# MCU_STM32F407VGT6.net
KiCad netlist of a schematic drawn in Altium Designer
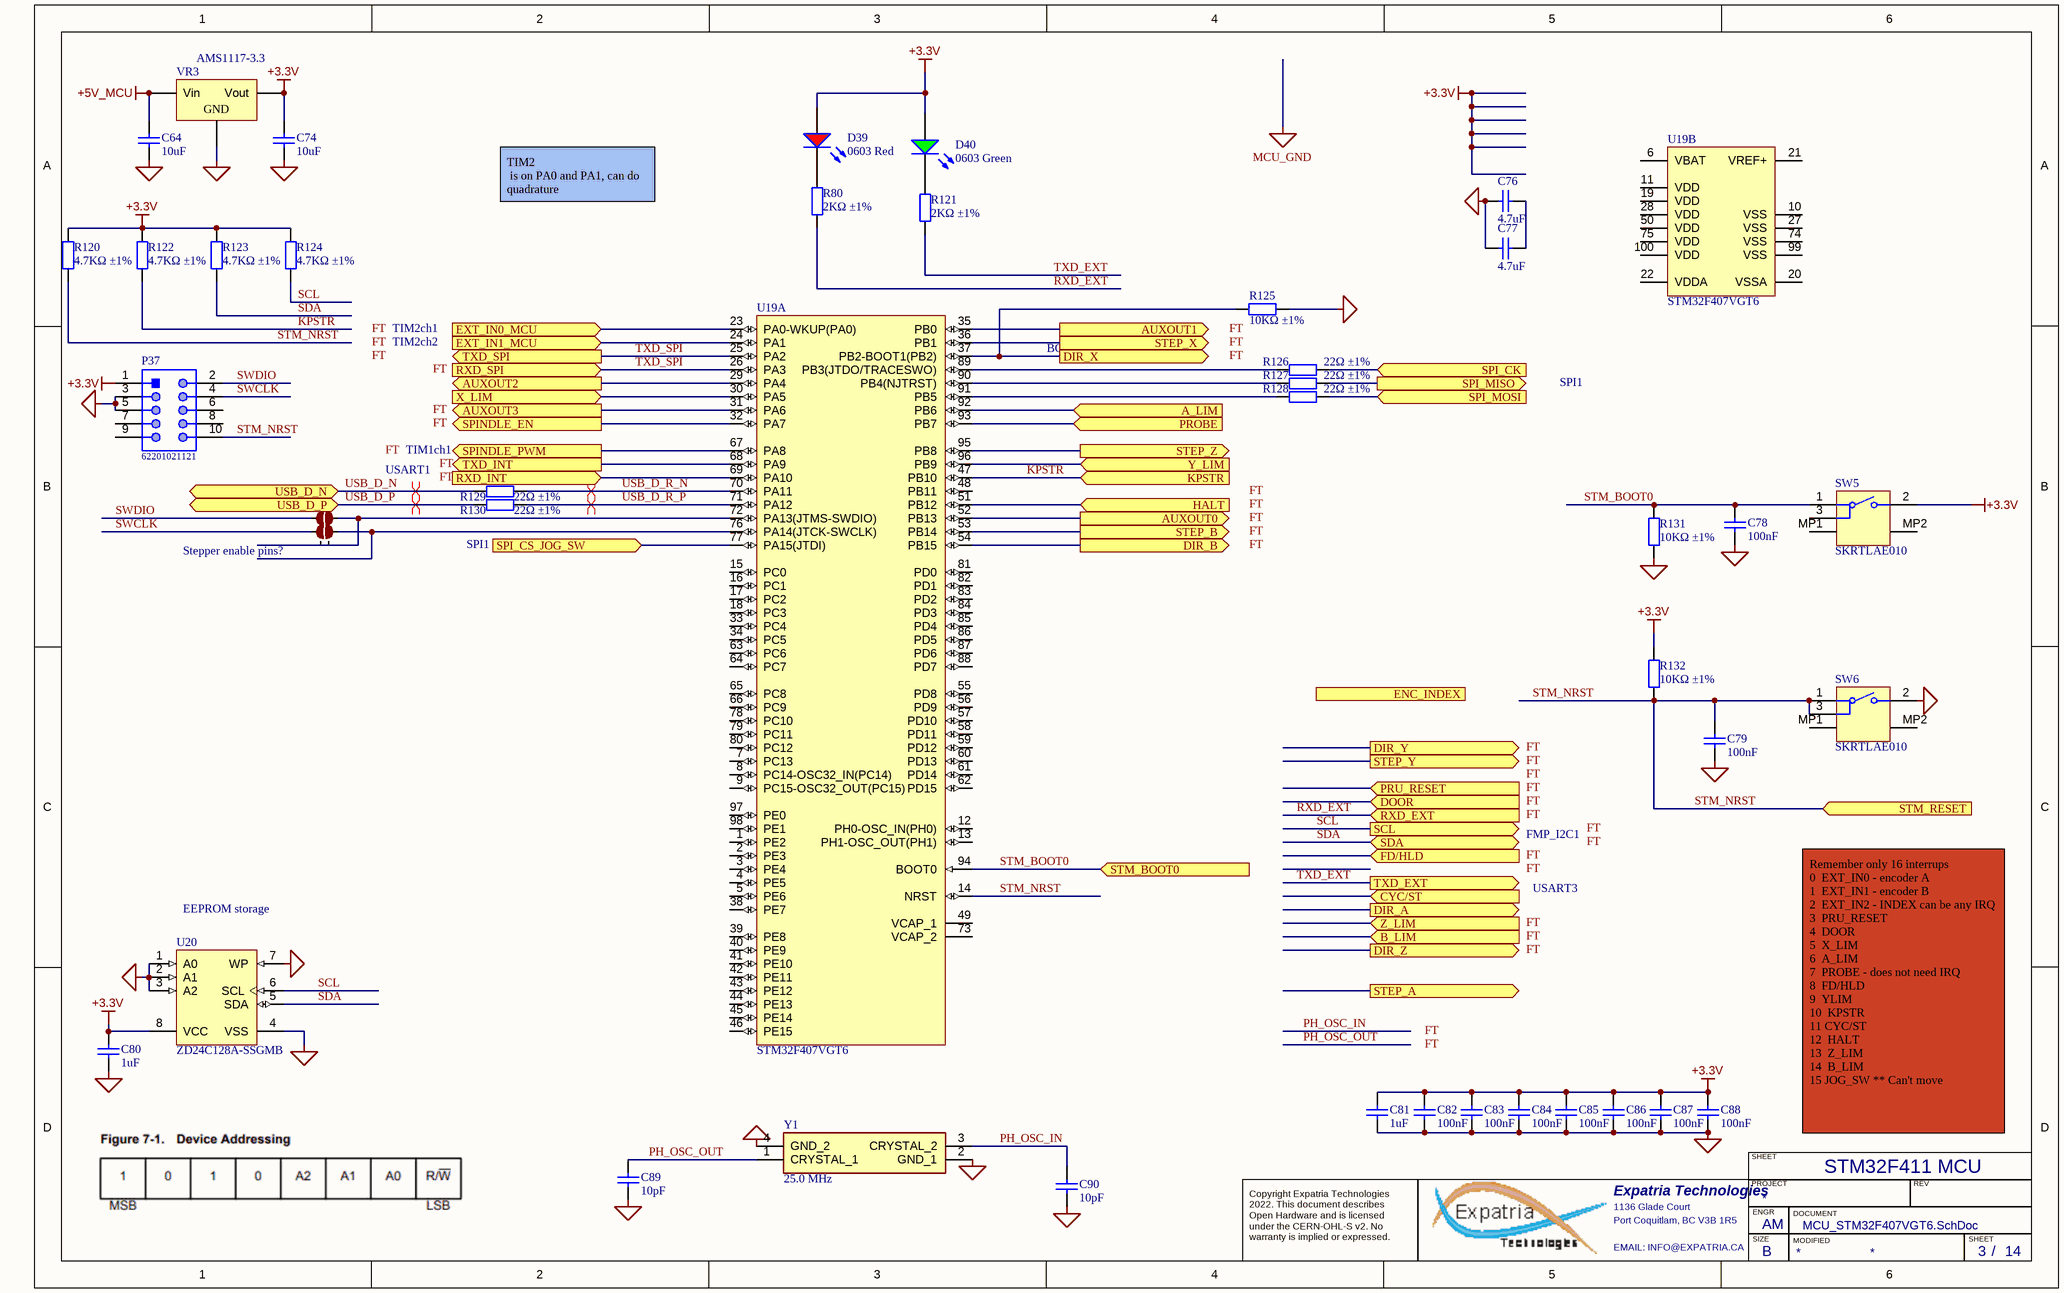
[diagram p0: MCU_STM32F407VGT6.SchDoc]

(export (version "E")
  (design (tool "Eeschema 10.0.6"))
  (components
    (comp (ref "C64")
      (value "10uF")
      (footprint "1206_C")
      (description "Chip capacitors")
      (fields
        (field (name "MANUFACTURER") "Samsung Electro-Mechanics")
        (field (name "PARTNUMBER") "CL31A106KBHNNNE")
      )
      (libsource (lib "Cap") (part "1206 10uF (106) 10% 50V"))
    )
    (comp (ref "C74")
      (value "10uF")
      (footprint "1206_C")
      (description "Chip capacitors")
      (fields
        (field (name "MANUFACTURER") "Samsung Electro-Mechanics")
        (field (name "PARTNUMBER") "CL31A106KBHNNNE")
      )
      (libsource (lib "Cap") (part "1206 10uF (106) 10% 50V"))
    )
    (comp (ref "C76")
      (value "4.7uF")
      (footprint "0603_C")
      (description "Chip capacitors")
      (fields
        (field (name "MANUFACTURER") "Samsung Electro-Mechanics")
        (field (name "PARTNUMBER") "CL10A475KO8NNNC")
      )
      (libsource (lib "Cap") (part "0603 4.7uF (475) 10% 16V"))
    )
    (comp (ref "C77")
      (value "4.7uF")
      (footprint "0603_C")
      (description "Chip capacitors")
      (fields
        (field (name "MANUFACTURER") "Samsung Electro-Mechanics")
        (field (name "PARTNUMBER") "CL10A475KO8NNNC")
      )
      (libsource (lib "Cap") (part "0603 4.7uF (475) 10% 16V"))
    )
    (comp (ref "C78")
      (value "100nF")
      (footprint "0603_C")
      (description "Chip capacitors")
      (fields (field (name "MANUFACTURER") "YAGEO") (field (name "PARTNUMBER") "CC0603KRX7R9BB104"))
      (libsource (lib "Cap") (part "0603 100nF (104) 10% 50V"))
    )
    (comp (ref "C79")
      (value "100nF")
      (footprint "0603_C")
      (description "Chip capacitors")
      (fields (field (name "MANUFACTURER") "YAGEO") (field (name "PARTNUMBER") "CC0603KRX7R9BB104"))
      (libsource (lib "Cap") (part "0603 100nF (104) 10% 50V"))
    )
    (comp (ref "C80")
      (value "1uF")
      (footprint "0603_C")
      (description "Chip capacitors")
      (fields
        (field (name "MANUFACTURER") "Samsung Electro-Mechanics")
        (field (name "PARTNUMBER") "CL10A105KB8NNNC")
      )
      (libsource (lib "Cap") (part "0603 1uF (105) 10% 50V"))
    )
    (comp (ref "C81")
      (value "1uF")
      (footprint "0603_C")
      (description "Chip capacitors")
      (fields
        (field (name "MANUFACTURER") "Samsung Electro-Mechanics")
        (field (name "PARTNUMBER") "CL10A105KB8NNNC")
      )
      (libsource (lib "Cap") (part "0603 1uF (105) 10% 50V"))
    )
    (comp (ref "C82")
      (value "100nF")
      (footprint "0603_C")
      (description "Chip capacitors")
      (fields (field (name "MANUFACTURER") "YAGEO") (field (name "PARTNUMBER") "CC0603KRX7R9BB104"))
      (libsource (lib "Cap") (part "0603 100nF (104) 10% 50V"))
    )
    (comp (ref "C83")
      (value "100nF")
      (footprint "0603_C")
      (description "Chip capacitors")
      (fields (field (name "MANUFACTURER") "YAGEO") (field (name "PARTNUMBER") "CC0603KRX7R9BB104"))
      (libsource (lib "Cap") (part "0603 100nF (104) 10% 50V"))
    )
    (comp (ref "C84")
      (value "100nF")
      (footprint "0603_C")
      (description "Chip capacitors")
      (fields (field (name "MANUFACTURER") "YAGEO") (field (name "PARTNUMBER") "CC0603KRX7R9BB104"))
      (libsource (lib "Cap") (part "0603 100nF (104) 10% 50V"))
    )
    (comp (ref "C85")
      (value "100nF")
      (footprint "0603_C")
      (description "Chip capacitors")
      (fields (field (name "MANUFACTURER") "YAGEO") (field (name "PARTNUMBER") "CC0603KRX7R9BB104"))
      (libsource (lib "Cap") (part "0603 100nF (104) 10% 50V"))
    )
    (comp (ref "C86")
      (value "100nF")
      (footprint "0603_C")
      (description "Chip capacitors")
      (fields (field (name "MANUFACTURER") "YAGEO") (field (name "PARTNUMBER") "CC0603KRX7R9BB104"))
      (libsource (lib "Cap") (part "0603 100nF (104) 10% 50V"))
    )
    (comp (ref "C87")
      (value "100nF")
      (footprint "0603_C")
      (description "Chip capacitors")
      (fields (field (name "MANUFACTURER") "YAGEO") (field (name "PARTNUMBER") "CC0603KRX7R9BB104"))
      (libsource (lib "Cap") (part "0603 100nF (104) 10% 50V"))
    )
    (comp (ref "C88")
      (value "100nF")
      (footprint "0603_C")
      (description "Chip capacitors")
      (fields (field (name "MANUFACTURER") "YAGEO") (field (name "PARTNUMBER") "CC0603KRX7R9BB104"))
      (libsource (lib "Cap") (part "0603 100nF (104) 10% 50V"))
    )
    (comp (ref "C89")
      (value "10pF")
      (footprint "0603_C")
      (description "Chip capacitors")
      (fields
        (field (name "MANUFACTURER") "Samsung Electro-Mechanics")
        (field (name "PARTNUMBER") "CL10C100JB8NNNC")
      )
      (libsource (lib "Cap") (part "0603 10pF (100) 5% 50V"))
    )
    (comp (ref "C90")
      (value "10pF")
      (footprint "0603_C")
      (description "Chip capacitors")
      (fields
        (field (name "MANUFACTURER") "Samsung Electro-Mechanics")
        (field (name "PARTNUMBER") "CL10C100JB8NNNC")
      )
      (libsource (lib "Cap") (part "0603 10pF (100) 5% 50V"))
    )
    (comp (ref "D39")
      (value "0603 Red")
      (footprint "0603_LED_S1")
      (description "LED")
      (libsource (lib "LED") (part "0603 LED Red"))
    )
    (comp (ref "D40")
      (value "0603 Green")
      (footprint "0603_LED_S1")
      (description "LED")
      (libsource (lib "LED") (part "0603 LED Green"))
    )
    (comp (ref "J14")
      (value "2 way net solder junction - Normally Open")
      (footprint "2waySolder_NO")
      (libsource (lib "PrintNC_GRBLHAL_Breakout") (part "2waySolderNO"))
    )
    (comp (ref "J15")
      (value "2 way net solder junction - Normally Open")
      (footprint "2waySolder_NO")
      (libsource (lib "PrintNC_GRBLHAL_Breakout") (part "2waySolderNO"))
    )
    (comp (ref "P37")
      (value "62201021121")
      (footprint "62201021121")
      (description "THT Vertical Pin Header WR-PHD, Pitch 1.27 mm, Dual Row, 10 pins")
      (fields (field (name "MANUFACTURER") "Wurth Elektronik") (field (name "PUBLISHER") "WurthElektronik"))
      (libsource (lib "Altium Content Vault") (part "WE-CN-2P-M-R10"))
    )
    (comp (ref "R80")
      (value "2KΩ ±1%")
      (footprint "0603_R")
      (description "Chip resistor")
      (fields (field (name "MANUFACTURER") "Uniroyal Elec") (field (name "PARTNUMBER") "0603WAF2001T5E"))
      (libsource (lib "RES") (part "0603 2K (2001) 1%"))
    )
    (comp (ref "R120")
      (value "4.7KΩ ±1%")
      (footprint "0603_R")
      (description "Chip resistor")
      (fields (field (name "MANUFACTURER") "Uniroyal Elec") (field (name "PARTNUMBER") "0603WAF4701T5E"))
      (libsource (lib "RES") (part "0603 4.7K (4701) 1%"))
    )
    (comp (ref "R121")
      (value "2KΩ ±1%")
      (footprint "0603_R")
      (description "Chip resistor")
      (fields (field (name "MANUFACTURER") "Uniroyal Elec") (field (name "PARTNUMBER") "0603WAF2001T5E"))
      (libsource (lib "RES") (part "0603 2K (2001) 1%"))
    )
    (comp (ref "R122")
      (value "4.7KΩ ±1%")
      (footprint "0603_R")
      (description "Chip resistor")
      (fields (field (name "MANUFACTURER") "Uniroyal Elec") (field (name "PARTNUMBER") "0603WAF4701T5E"))
      (libsource (lib "RES") (part "0603 4.7K (4701) 1%"))
    )
    (comp (ref "R123")
      (value "4.7KΩ ±1%")
      (footprint "0603_R")
      (description "Chip resistor")
      (fields (field (name "MANUFACTURER") "Uniroyal Elec") (field (name "PARTNUMBER") "0603WAF4701T5E"))
      (libsource (lib "RES") (part "0603 4.7K (4701) 1%"))
    )
    (comp (ref "R124")
      (value "4.7KΩ ±1%")
      (footprint "0603_R")
      (description "Chip resistor")
      (fields (field (name "MANUFACTURER") "Uniroyal Elec") (field (name "PARTNUMBER") "0603WAF4701T5E"))
      (libsource (lib "RES") (part "0603 4.7K (4701) 1%"))
    )
    (comp (ref "R125")
      (value "10KΩ ±1%")
      (footprint "0603_R")
      (description "Chip resistor")
      (fields (field (name "MANUFACTURER") "Uniroyal Elec") (field (name "PARTNUMBER") "0603WAF1002T5E"))
      (libsource (lib "RES") (part "0603 10K (1002) 1%"))
    )
    (comp (ref "R126")
      (value "22Ω ±1%")
      (footprint "0603_R")
      (description "Chip resistor")
      (fields (field (name "MANUFACTURER") "Uniroyal Elec") (field (name "PARTNUMBER") "0603WAF220JT5E"))
      (libsource (lib "") (part "0603 22R (22R0) 1%_1"))
    )
    (comp (ref "R127")
      (value "22Ω ±1%")
      (footprint "0603_R")
      (description "Chip resistor")
      (fields (field (name "MANUFACTURER") "Uniroyal Elec") (field (name "PARTNUMBER") "0603WAF220JT5E"))
      (libsource (lib "") (part "0603 22R (22R0) 1%_1"))
    )
    (comp (ref "R128")
      (value "22Ω ±1%")
      (footprint "0603_R")
      (description "Chip resistor")
      (fields (field (name "MANUFACTURER") "Uniroyal Elec") (field (name "PARTNUMBER") "0603WAF220JT5E"))
      (libsource (lib "") (part "0603 22R (22R0) 1%_1"))
    )
    (comp (ref "R129")
      (value "22Ω ±1%")
      (footprint "0603_R")
      (description "Chip resistor")
      (fields (field (name "MANUFACTURER") "Uniroyal Elec") (field (name "PARTNUMBER") "0603WAF220JT5E"))
      (libsource (lib "RES") (part "0603 22R (22R0) 1%"))
    )
    (comp (ref "R130")
      (value "22Ω ±1%")
      (footprint "0603_R")
      (description "Chip resistor")
      (fields (field (name "MANUFACTURER") "Uniroyal Elec") (field (name "PARTNUMBER") "0603WAF220JT5E"))
      (libsource (lib "RES") (part "0603 22R (22R0) 1%"))
    )
    (comp (ref "R131")
      (value "10KΩ ±1%")
      (footprint "0603_R")
      (description "Chip resistor")
      (fields (field (name "MANUFACTURER") "Uniroyal Elec") (field (name "PARTNUMBER") "0603WAF1002T5E"))
      (libsource (lib "RES") (part "0603 10K (1002) 1%"))
    )
    (comp (ref "R132")
      (value "10KΩ ±1%")
      (footprint "0603_R")
      (description "Chip resistor")
      (fields (field (name "MANUFACTURER") "Uniroyal Elec") (field (name "PARTNUMBER") "0603WAF1002T5E"))
      (libsource (lib "RES") (part "0603 10K (1002) 1%"))
    )
    (comp (ref "SW5")
      (value "SKRTLAE010")
      (footprint "ALPS-SKRTLAE010_V")
      (description "Side Push Type, 250 V, -40 to 90 degC, 3-Pin SMD, RoHS, Tape and Reel")
      (fields (field (name "MANUFACTURER") "ALPS"))
      (libsource (lib "Altium Content Vault") (part "SW_SPST-3_A"))
    )
    (comp (ref "SW6")
      (value "SKRTLAE010")
      (footprint "ALPS-SKRTLAE010_V")
      (description "Side Push Type, 250 V, -40 to 90 degC, 3-Pin SMD, RoHS, Tape and Reel")
      (fields (field (name "MANUFACTURER") "ALPS"))
      (libsource (lib "Altium Content Vault") (part "SW_SPST-3_A"))
    )
    (comp (ref "U19")
      (value "STM32F407VGT6")
      (footprint "STM-LQFP100_M")
      (fields (field (name "MANUFACTURER") "STMicroelectronics"))
      (libsource (lib "Altium Content Vault") (part "MC-ARM-STM32F40X_41X-SQ100"))
    )
    (comp (ref "U20")
      (value "ZD24C128A-SSGMB")
      (footprint "SOIC-SN8_L")
      (description "IC EEPROM 128KBIT I2C 8SOIC")
      (libsource (lib "PrintNC_GRBLHAL_Breakout") (part "MEM-SEEPROM-34AA02-IL8"))
    )
    (comp (ref "VR3")
      (value "AMS1117-3.3")
      (footprint "SOT-223")
      (description "Vout=3.3V 1A 72dB@(120Hz) (LDO)")
      (libsource (lib "LDO") (part "SOT-223 AMS1117-3.3"))
    )
    (comp (ref "Y1")
      (value "25.0 MHz")
      (footprint "SamacSys:YSX321SL")
      (description "Crystal or Oscillator")
      (fields (field (name "MANUFACTURER_PART_NUMBER") "X322525MSB4SI"))
      (libsource (lib "*") (part "YSX321SL"))
    )
  )
  (nets
    (net (code "1") (name "+3.3V") (class "Default")
      (node (ref "C74") (pin "2") (pinfunction "2_2") (pintype "passive"))
      (node (ref "C80") (pin "2") (pinfunction "2_2") (pintype "passive"))
      (node (ref "C81") (pin "2") (pinfunction "2_2") (pintype "passive"))
      (node (ref "C82") (pin "2") (pinfunction "2_2") (pintype "passive"))
      (node (ref "C83") (pin "2") (pinfunction "2_2") (pintype "passive"))
      (node (ref "C84") (pin "2") (pinfunction "2_2") (pintype "passive"))
      (node (ref "C85") (pin "2") (pinfunction "2_2") (pintype "passive"))
      (node (ref "C86") (pin "2") (pinfunction "2_2") (pintype "passive"))
      (node (ref "C87") (pin "2") (pinfunction "2_2") (pintype "passive"))
      (node (ref "C88") (pin "2") (pinfunction "2_2") (pintype "passive"))
      (node (ref "D39") (pin "A") (pinfunction "A_A") (pintype "passive"))
      (node (ref "D40") (pin "A") (pinfunction "A_A") (pintype "passive"))
      (node (ref "P37") (pin "1") (pinfunction "1_1") (pintype "passive"))
      (node (ref "R120") (pin "2") (pinfunction "2_2") (pintype "passive"))
      (node (ref "R122") (pin "2") (pinfunction "2_2") (pintype "passive"))
      (node (ref "R123") (pin "2") (pinfunction "2_2") (pintype "passive"))
      (node (ref "R124") (pin "2") (pinfunction "2_2") (pintype "passive"))
      (node (ref "R132") (pin "1") (pinfunction "1_1") (pintype "passive"))
      (node (ref "SW5") (pin "2") (pinfunction "2_2") (pintype "passive"))
      (node (ref "U20") (pin "8") (pinfunction "VCC_8") (pintype "power_in"))
      (node (ref "VR3") (pin "2") (pinfunction "Vout_2") (pintype "passive"))
    )
    (net (code "2") (name "+5V_MCU") (class "Default")
      (node (ref "C64") (pin "2") (pinfunction "2_2") (pintype "passive"))
      (node (ref "VR3") (pin "3") (pinfunction "Vin_3") (pintype "passive"))
    )
    (net (code "3") (name "/AUXOUT0") (class "Default")
      (node (ref "U19") (pin "52") (pinfunction "PB13_52") (pintype "bidirectional"))
    )
    (net (code "4") (name "/AUXOUT1") (class "Default")
      (node (ref "U19") (pin "35") (pinfunction "PB0_35") (pintype "bidirectional"))
    )
    (net (code "5") (name "/AUXOUT2") (class "Default")
      (node (ref "U19") (pin "29") (pinfunction "PA4_29") (pintype "bidirectional"))
    )
    (net (code "6") (name "/AUXOUT3") (class "Default")
      (node (ref "U19") (pin "31") (pinfunction "PA6_31") (pintype "bidirectional"))
    )
    (net (code "7") (name "/A_LIM") (class "Default")
      (node (ref "U19") (pin "92") (pinfunction "PB6_92") (pintype "bidirectional"))
    )
    (net (code "11") (name "/DIR_B") (class "Default")
      (node (ref "U19") (pin "54") (pinfunction "PB15_54") (pintype "bidirectional"))
    )
    (net (code "12") (name "/DIR_X") (class "Default")
      (node (ref "R125") (pin "2") (pinfunction "2_2") (pintype "passive"))
      (node (ref "U19") (pin "37") (pinfunction "PB2-BOOT1(PB2)_37") (pintype "bidirectional"))
    )
    (net (code "17") (name "/EXT_IN0_MCU") (class "Default")
      (node (ref "U19") (pin "23") (pinfunction "PA0-WKUP(PA0)_23") (pintype "bidirectional"))
    )
    (net (code "18") (name "/EXT_IN1_MCU") (class "Default")
      (node (ref "U19") (pin "24") (pinfunction "PA1_24") (pintype "bidirectional"))
    )
    (net (code "20") (name "/HALT") (class "Default")
      (node (ref "U19") (pin "51") (pinfunction "PB12_51") (pintype "bidirectional"))
    )
    (net (code "21") (name "/KPSTR") (class "Default")
      (node (ref "R122") (pin "1") (pinfunction "1_1") (pintype "passive"))
      (node (ref "U19") (pin "47") (pinfunction "PB10_47") (pintype "bidirectional"))
    )
    (net (code "22") (name "/PH_OSC_IN") (class "Default")
      (node (ref "C90") (pin "2") (pinfunction "2_2") (pintype "passive"))
      (node (ref "Y1") (pin "3") (pinfunction "CRYSTAL_2_3") (pintype "passive"))
    )
    (net (code "23") (name "/PH_OSC_OUT") (class "Default")
      (node (ref "C89") (pin "2") (pinfunction "2_2") (pintype "passive"))
      (node (ref "Y1") (pin "1") (pinfunction "CRYSTAL_1_1") (pintype "passive"))
    )
    (net (code "24") (name "/PROBE") (class "Default")
      (node (ref "U19") (pin "93") (pinfunction "PB7_93") (pintype "bidirectional"))
    )
    (net (code "26") (name "/RXD_EXT") (class "Default")
      (node (ref "R80") (pin "1") (pinfunction "1_1") (pintype "passive"))
    )
    (net (code "27") (name "/RXD_INT") (class "Default")
      (node (ref "U19") (pin "69") (pinfunction "PA10_69") (pintype "bidirectional"))
    )
    (net (code "28") (name "/SCL") (class "Default")
      (node (ref "R124") (pin "1") (pinfunction "1_1") (pintype "passive"))
      (node (ref "U20") (pin "6") (pinfunction "SCL_6") (pintype "input"))
    )
    (net (code "29") (name "/SDA") (class "Default")
      (node (ref "R123") (pin "1") (pinfunction "1_1") (pintype "passive"))
      (node (ref "U20") (pin "5") (pinfunction "SDA_5") (pintype "bidirectional"))
    )
    (net (code "30") (name "/SPINDLE_EN") (class "Default")
      (node (ref "U19") (pin "32") (pinfunction "PA7_32") (pintype "bidirectional"))
    )
    (net (code "31") (name "/SPINDLE_PWM") (class "Default")
      (node (ref "U19") (pin "67") (pinfunction "PA8_67") (pintype "bidirectional"))
    )
    (net (code "32") (name "/SPI_CK") (class "Default")
      (node (ref "R126") (pin "2") (pinfunction "2_2") (pintype "passive"))
    )
    (net (code "33") (name "/SPI_CS_JOG_SW") (class "Default")
      (node (ref "U19") (pin "77") (pinfunction "PA15(JTDI)_77") (pintype "bidirectional"))
    )
    (net (code "34") (name "/SPI_MISO") (class "Default")
      (node (ref "R127") (pin "2") (pinfunction "2_2") (pintype "passive"))
    )
    (net (code "35") (name "/SPI_MOSI") (class "Default")
      (node (ref "R128") (pin "2") (pinfunction "2_2") (pintype "passive"))
    )
    (net (code "37") (name "/STEP_B") (class "Default")
      (node (ref "U19") (pin "53") (pinfunction "PB14_53") (pintype "bidirectional"))
    )
    (net (code "38") (name "/STEP_X") (class "Default")
      (node (ref "U19") (pin "36") (pinfunction "PB1_36") (pintype "bidirectional"))
    )
    (net (code "40") (name "/STEP_Z") (class "Default")
      (node (ref "U19") (pin "95") (pinfunction "PB8_95") (pintype "bidirectional"))
    )
    (net (code "41") (name "/STM_BOOT0") (class "Default")
      (node (ref "C78") (pin "2") (pinfunction "2_2") (pintype "passive"))
      (node (ref "R131") (pin "1") (pinfunction "1_1") (pintype "passive"))
      (node (ref "SW5") (pin "1") (pinfunction "1_1") (pintype "passive"))
      (node (ref "U19") (pin "94") (pinfunction "BOOT0_94") (pintype "input"))
    )
    (net (code "42") (name "/STM_NRST") (class "Default")
      (node (ref "C79") (pin "2") (pinfunction "2_2") (pintype "passive"))
      (node (ref "P37") (pin "10") (pinfunction "10_10") (pintype "passive"))
      (node (ref "R120") (pin "1") (pinfunction "1_1") (pintype "passive"))
      (node (ref "R132") (pin "2") (pinfunction "2_2") (pintype "passive"))
      (node (ref "SW6") (pin "1") (pinfunction "1_1") (pintype "passive"))
      (node (ref "SW6") (pin "3") (pinfunction "3_3") (pintype "passive"))
      (node (ref "U19") (pin "14") (pinfunction "NRST_14") (pintype "bidirectional"))
    )
    (net (code "43") (name "/SWCLK") (class "Default")
      (node (ref "J15") (pin "1") (pinfunction "1_1") (pintype "passive"))
      (node (ref "P37") (pin "4") (pinfunction "4_4") (pintype "passive"))
    )
    (net (code "44") (name "/SWDIO") (class "Default")
      (node (ref "J14") (pin "1") (pinfunction "1_1") (pintype "passive"))
      (node (ref "P37") (pin "2") (pinfunction "2_2") (pintype "passive"))
    )
    (net (code "45") (name "/TXD_EXT") (class "Default")
      (node (ref "R121") (pin "1") (pinfunction "1_1") (pintype "passive"))
    )
    (net (code "46") (name "/TXD_INT") (class "Default")
      (node (ref "U19") (pin "68") (pinfunction "PA9_68") (pintype "bidirectional"))
    )
    (net (code "47") (name "/TXD_SPI") (class "Default")
      (node (ref "U19") (pin "25") (pinfunction "PA2_25") (pintype "bidirectional"))
      (node (ref "U19") (pin "26") (pinfunction "PA3_26") (pintype "bidirectional"))
    )
    (net (code "48") (name "/USB_D_N") (class "Default")
      (node (ref "R129") (pin "2") (pinfunction "2_2") (pintype "passive"))
    )
    (net (code "49") (name "/USB_D_P") (class "Default")
      (node (ref "R130") (pin "2") (pinfunction "2_2") (pintype "passive"))
    )
    (net (code "50") (name "/USB_D_R_N") (class "Default")
      (node (ref "R129") (pin "1") (pinfunction "1_1") (pintype "passive"))
      (node (ref "U19") (pin "70") (pinfunction "PA11_70") (pintype "bidirectional"))
    )
    (net (code "51") (name "/USB_D_R_P") (class "Default")
      (node (ref "R130") (pin "1") (pinfunction "1_1") (pintype "passive"))
      (node (ref "U19") (pin "71") (pinfunction "PA12_71") (pintype "bidirectional"))
    )
    (net (code "52") (name "/X_LIM") (class "Default")
      (node (ref "U19") (pin "30") (pinfunction "PA5_30") (pintype "bidirectional"))
    )
    (net (code "53") (name "/Y_LIM") (class "Default")
      (node (ref "U19") (pin "96") (pinfunction "PB9_96") (pintype "bidirectional"))
    )
    (net (code "55") (name "MCU_GND") (class "Default")
      (node (ref "C64") (pin "1") (pinfunction "1_1") (pintype "passive"))
      (node (ref "C74") (pin "1") (pinfunction "1_1") (pintype "passive"))
      (node (ref "C76") (pin "1") (pinfunction "1_1") (pintype "passive"))
      (node (ref "C77") (pin "1") (pinfunction "1_1") (pintype "passive"))
      (node (ref "C78") (pin "1") (pinfunction "1_1") (pintype "passive"))
      (node (ref "C79") (pin "1") (pinfunction "1_1") (pintype "passive"))
      (node (ref "C80") (pin "1") (pinfunction "1_1") (pintype "passive"))
      (node (ref "C81") (pin "1") (pinfunction "1_1") (pintype "passive"))
      (node (ref "C82") (pin "1") (pinfunction "1_1") (pintype "passive"))
      (node (ref "C83") (pin "1") (pinfunction "1_1") (pintype "passive"))
      (node (ref "C84") (pin "1") (pinfunction "1_1") (pintype "passive"))
      (node (ref "C85") (pin "1") (pinfunction "1_1") (pintype "passive"))
      (node (ref "C86") (pin "1") (pinfunction "1_1") (pintype "passive"))
      (node (ref "C87") (pin "1") (pinfunction "1_1") (pintype "passive"))
      (node (ref "C88") (pin "1") (pinfunction "1_1") (pintype "passive"))
      (node (ref "C89") (pin "1") (pinfunction "1_1") (pintype "passive"))
      (node (ref "C90") (pin "1") (pinfunction "1_1") (pintype "passive"))
      (node (ref "P37") (pin "3") (pinfunction "3_3") (pintype "passive"))
      (node (ref "P37") (pin "5") (pinfunction "5_5") (pintype "passive"))
      (node (ref "R125") (pin "1") (pinfunction "1_1") (pintype "passive"))
      (node (ref "R131") (pin "2") (pinfunction "2_2") (pintype "passive"))
      (node (ref "SW6") (pin "2") (pinfunction "2_2") (pintype "passive"))
      (node (ref "U20") (pin "1") (pinfunction "A0_1") (pintype "input"))
      (node (ref "U20") (pin "2") (pinfunction "A1_2") (pintype "input"))
      (node (ref "U20") (pin "3") (pinfunction "A2_3") (pintype "input"))
      (node (ref "U20") (pin "4") (pinfunction "VSS_4") (pintype "power_in"))
      (node (ref "U20") (pin "7") (pinfunction "WP_7") (pintype "input"))
      (node (ref "VR3") (pin "1") (pinfunction "GND_1") (pintype "passive"))
      (node (ref "Y1") (pin "2") (pinfunction "GND_1_2") (pintype "passive"))
      (node (ref "Y1") (pin "4") (pinfunction "GND_2_4") (pintype "passive"))
    )
    (net (code "56") (name "Net-(C76-Pad2)") (class "Default")
      (node (ref "C76") (pin "2") (pinfunction "2_2") (pintype "passive"))
      (node (ref "C77") (pin "2") (pinfunction "2_2") (pintype "passive"))
    )
    (net (code "57") (name "Net-(D39-PadK)") (class "Default")
      (node (ref "D39") (pin "K") (pinfunction "K_K") (pintype "passive"))
      (node (ref "R80") (pin "2") (pinfunction "2_2") (pintype "passive"))
    )
    (net (code "58") (name "Net-(D40-PadK)") (class "Default")
      (node (ref "D40") (pin "K") (pinfunction "K_K") (pintype "passive"))
      (node (ref "R121") (pin "2") (pinfunction "2_2") (pintype "passive"))
    )
    (net (code "59") (name "Net-(U19A-PA13(JTMS-SWDIO))") (class "Default")
      (node (ref "J14") (pin "2") (pinfunction "2_2") (pintype "passive"))
      (node (ref "U19") (pin "72") (pinfunction "PA13(JTMS-SWDIO)_72") (pintype "bidirectional"))
    )
    (net (code "60") (name "Net-(U19A-PA14(JTCK-SWCLK))") (class "Default")
      (node (ref "J15") (pin "2") (pinfunction "2_2") (pintype "passive"))
      (node (ref "U19") (pin "76") (pinfunction "PA14(JTCK-SWCLK)_76") (pintype "bidirectional"))
    )
    (net (code "61") (name "Net-(U19A-PB3(JTDO{slash}TRACESWO))") (class "Default")
      (node (ref "R126") (pin "1") (pinfunction "1_1") (pintype "passive"))
      (node (ref "U19") (pin "89") (pinfunction "PB3(JTDO/TRACESWO)_89") (pintype "bidirectional"))
    )
    (net (code "62") (name "Net-(U19A-PB4(NJTRST))") (class "Default")
      (node (ref "R127") (pin "1") (pinfunction "1_1") (pintype "passive"))
      (node (ref "U19") (pin "90") (pinfunction "PB4(NJTRST)_90") (pintype "bidirectional"))
    )
    (net (code "63") (name "Net-(U19A-PB5)") (class "Default")
      (node (ref "R128") (pin "1") (pinfunction "1_1") (pintype "passive"))
      (node (ref "U19") (pin "91") (pinfunction "PB5_91") (pintype "bidirectional"))
    )
    (net (code "64") (name "unconnected-(P37-Pad6)") (class "Default")
      (node (ref "P37") (pin "6") (pinfunction "6_6") (pintype "passive"))
    )
    (net (code "65") (name "unconnected-(P37-Pad7)") (class "Default")
      (node (ref "P37") (pin "7") (pinfunction "7_7") (pintype "passive"))
    )
    (net (code "66") (name "unconnected-(P37-Pad8)") (class "Default")
      (node (ref "P37") (pin "8") (pinfunction "8_8") (pintype "passive"))
    )
    (net (code "67") (name "unconnected-(P37-Pad9)") (class "Default")
      (node (ref "P37") (pin "9") (pinfunction "9_9") (pintype "passive"))
    )
    (net (code "68") (name "unconnected-(SW5-Pad3)") (class "Default")
      (node (ref "SW5") (pin "3") (pinfunction "3_3") (pintype "passive"))
    )
    (net (code "69") (name "unconnected-(SW5-PadMP1)") (class "Default")
      (node (ref "SW5") (pin "MP1") (pinfunction "MP1_MP1") (pintype "passive"))
    )
    (net (code "70") (name "unconnected-(SW5-PadMP2)") (class "Default")
      (node (ref "SW5") (pin "MP2") (pinfunction "MP2_MP2") (pintype "passive"))
    )
    (net (code "71") (name "unconnected-(SW6-PadMP1)") (class "Default")
      (node (ref "SW6") (pin "MP1") (pinfunction "MP1_MP1") (pintype "passive"))
    )
    (net (code "72") (name "unconnected-(SW6-PadMP2)") (class "Default")
      (node (ref "SW6") (pin "MP2") (pinfunction "MP2_MP2") (pintype "passive"))
    )
    (net (code "73") (name "unconnected-(U19A-PB11-Pad48)") (class "Default")
      (node (ref "U19") (pin "48") (pinfunction "PB11_48") (pintype "bidirectional"))
    )
    (net (code "74") (name "unconnected-(U19A-PC0-Pad15)") (class "Default")
      (node (ref "U19") (pin "15") (pinfunction "PC0_15") (pintype "bidirectional"))
    )
    (net (code "75") (name "unconnected-(U19A-PC1-Pad16)") (class "Default")
      (node (ref "U19") (pin "16") (pinfunction "PC1_16") (pintype "bidirectional"))
    )
    (net (code "76") (name "unconnected-(U19A-PC2-Pad17)") (class "Default")
      (node (ref "U19") (pin "17") (pinfunction "PC2_17") (pintype "bidirectional"))
    )
    (net (code "77") (name "unconnected-(U19A-PC3-Pad18)") (class "Default")
      (node (ref "U19") (pin "18") (pinfunction "PC3_18") (pintype "bidirectional"))
    )
    (net (code "78") (name "unconnected-(U19A-PC4-Pad33)") (class "Default")
      (node (ref "U19") (pin "33") (pinfunction "PC4_33") (pintype "bidirectional"))
    )
    (net (code "79") (name "unconnected-(U19A-PC5-Pad34)") (class "Default")
      (node (ref "U19") (pin "34") (pinfunction "PC5_34") (pintype "bidirectional"))
    )
    (net (code "80") (name "unconnected-(U19A-PC6-Pad63)") (class "Default")
      (node (ref "U19") (pin "63") (pinfunction "PC6_63") (pintype "bidirectional"))
    )
    (net (code "81") (name "unconnected-(U19A-PC7-Pad64)") (class "Default")
      (node (ref "U19") (pin "64") (pinfunction "PC7_64") (pintype "bidirectional"))
    )
    (net (code "82") (name "unconnected-(U19A-PC8-Pad65)") (class "Default")
      (node (ref "U19") (pin "65") (pinfunction "PC8_65") (pintype "bidirectional"))
    )
    (net (code "83") (name "unconnected-(U19A-PC9-Pad66)") (class "Default")
      (node (ref "U19") (pin "66") (pinfunction "PC9_66") (pintype "bidirectional"))
    )
    (net (code "84") (name "unconnected-(U19A-PC10-Pad78)") (class "Default")
      (node (ref "U19") (pin "78") (pinfunction "PC10_78") (pintype "bidirectional"))
    )
    (net (code "85") (name "unconnected-(U19A-PC11-Pad79)") (class "Default")
      (node (ref "U19") (pin "79") (pinfunction "PC11_79") (pintype "bidirectional"))
    )
    (net (code "86") (name "unconnected-(U19A-PC12-Pad80)") (class "Default")
      (node (ref "U19") (pin "80") (pinfunction "PC12_80") (pintype "bidirectional"))
    )
    (net (code "87") (name "unconnected-(U19A-PC13-Pad7)") (class "Default")
      (node (ref "U19") (pin "7") (pinfunction "PC13_7") (pintype "bidirectional"))
    )
    (net (code "88") (name "unconnected-(U19A-PC14-OSC32_IN(PC14)-Pad8)") (class "Default")
      (node (ref "U19") (pin "8") (pinfunction "PC14-OSC32_IN(PC14)_8") (pintype "bidirectional"))
    )
    (net (code "89") (name "unconnected-(U19A-PC15-OSC32_OUT(PC15)-Pad9)") (class "Default")
      (node (ref "U19") (pin "9") (pinfunction "PC15-OSC32_OUT(PC15)_9") (pintype "bidirectional"))
    )
    (net (code "90") (name "unconnected-(U19A-PD0-Pad81)") (class "Default")
      (node (ref "U19") (pin "81") (pinfunction "PD0_81") (pintype "bidirectional"))
    )
    (net (code "91") (name "unconnected-(U19A-PD1-Pad82)") (class "Default")
      (node (ref "U19") (pin "82") (pinfunction "PD1_82") (pintype "bidirectional"))
    )
    (net (code "92") (name "unconnected-(U19A-PD2-Pad83)") (class "Default")
      (node (ref "U19") (pin "83") (pinfunction "PD2_83") (pintype "bidirectional"))
    )
    (net (code "93") (name "unconnected-(U19A-PD3-Pad84)") (class "Default")
      (node (ref "U19") (pin "84") (pinfunction "PD3_84") (pintype "bidirectional"))
    )
    (net (code "94") (name "unconnected-(U19A-PD4-Pad85)") (class "Default")
      (node (ref "U19") (pin "85") (pinfunction "PD4_85") (pintype "bidirectional"))
    )
    (net (code "95") (name "unconnected-(U19A-PD5-Pad86)") (class "Default")
      (node (ref "U19") (pin "86") (pinfunction "PD5_86") (pintype "bidirectional"))
    )
    (net (code "96") (name "unconnected-(U19A-PD6-Pad87)") (class "Default")
      (node (ref "U19") (pin "87") (pinfunction "PD6_87") (pintype "bidirectional"))
    )
    (net (code "97") (name "unconnected-(U19A-PD7-Pad88)") (class "Default")
      (node (ref "U19") (pin "88") (pinfunction "PD7_88") (pintype "bidirectional"))
    )
    (net (code "98") (name "unconnected-(U19A-PD8-Pad55)") (class "Default")
      (node (ref "U19") (pin "55") (pinfunction "PD8_55") (pintype "bidirectional"))
    )
    (net (code "99") (name "unconnected-(U19A-PD9-Pad56)") (class "Default")
      (node (ref "U19") (pin "56") (pinfunction "PD9_56") (pintype "bidirectional"))
    )
    (net (code "100") (name "unconnected-(U19A-PD10-Pad57)") (class "Default")
      (node (ref "U19") (pin "57") (pinfunction "PD10_57") (pintype "bidirectional"))
    )
    (net (code "101") (name "unconnected-(U19A-PD11-Pad58)") (class "Default")
      (node (ref "U19") (pin "58") (pinfunction "PD11_58") (pintype "bidirectional"))
    )
    (net (code "102") (name "unconnected-(U19A-PD12-Pad59)") (class "Default")
      (node (ref "U19") (pin "59") (pinfunction "PD12_59") (pintype "bidirectional"))
    )
    (net (code "103") (name "unconnected-(U19A-PD13-Pad60)") (class "Default")
      (node (ref "U19") (pin "60") (pinfunction "PD13_60") (pintype "bidirectional"))
    )
    (net (code "104") (name "unconnected-(U19A-PD14-Pad61)") (class "Default")
      (node (ref "U19") (pin "61") (pinfunction "PD14_61") (pintype "bidirectional"))
    )
    (net (code "105") (name "unconnected-(U19A-PD15-Pad62)") (class "Default")
      (node (ref "U19") (pin "62") (pinfunction "PD15_62") (pintype "bidirectional"))
    )
    (net (code "106") (name "unconnected-(U19A-PE0-Pad97)") (class "Default")
      (node (ref "U19") (pin "97") (pinfunction "PE0_97") (pintype "bidirectional"))
    )
    (net (code "107") (name "unconnected-(U19A-PE1-Pad98)") (class "Default")
      (node (ref "U19") (pin "98") (pinfunction "PE1_98") (pintype "bidirectional"))
    )
    (net (code "108") (name "unconnected-(U19A-PE2-Pad1)") (class "Default")
      (node (ref "U19") (pin "1") (pinfunction "PE2_1") (pintype "bidirectional"))
    )
    (net (code "109") (name "unconnected-(U19A-PE3-Pad2)") (class "Default")
      (node (ref "U19") (pin "2") (pinfunction "PE3_2") (pintype "bidirectional"))
    )
    (net (code "110") (name "unconnected-(U19A-PE4-Pad3)") (class "Default")
      (node (ref "U19") (pin "3") (pinfunction "PE4_3") (pintype "bidirectional"))
    )
    (net (code "111") (name "unconnected-(U19A-PE5-Pad4)") (class "Default")
      (node (ref "U19") (pin "4") (pinfunction "PE5_4") (pintype "bidirectional"))
    )
    (net (code "112") (name "unconnected-(U19A-PE6-Pad5)") (class "Default")
      (node (ref "U19") (pin "5") (pinfunction "PE6_5") (pintype "bidirectional"))
    )
    (net (code "113") (name "unconnected-(U19A-PE7-Pad38)") (class "Default")
      (node (ref "U19") (pin "38") (pinfunction "PE7_38") (pintype "bidirectional"))
    )
    (net (code "114") (name "unconnected-(U19A-PE8-Pad39)") (class "Default")
      (node (ref "U19") (pin "39") (pinfunction "PE8_39") (pintype "bidirectional"))
    )
    (net (code "115") (name "unconnected-(U19A-PE9-Pad40)") (class "Default")
      (node (ref "U19") (pin "40") (pinfunction "PE9_40") (pintype "bidirectional"))
    )
    (net (code "116") (name "unconnected-(U19A-PE10-Pad41)") (class "Default")
      (node (ref "U19") (pin "41") (pinfunction "PE10_41") (pintype "bidirectional"))
    )
    (net (code "117") (name "unconnected-(U19A-PE11-Pad42)") (class "Default")
      (node (ref "U19") (pin "42") (pinfunction "PE11_42") (pintype "bidirectional"))
    )
    (net (code "118") (name "unconnected-(U19A-PE12-Pad43)") (class "Default")
      (node (ref "U19") (pin "43") (pinfunction "PE12_43") (pintype "bidirectional"))
    )
    (net (code "119") (name "unconnected-(U19A-PE13-Pad44)") (class "Default")
      (node (ref "U19") (pin "44") (pinfunction "PE13_44") (pintype "bidirectional"))
    )
    (net (code "120") (name "unconnected-(U19A-PE14-Pad45)") (class "Default")
      (node (ref "U19") (pin "45") (pinfunction "PE14_45") (pintype "bidirectional"))
    )
    (net (code "121") (name "unconnected-(U19A-PE15-Pad46)") (class "Default")
      (node (ref "U19") (pin "46") (pinfunction "PE15_46") (pintype "bidirectional"))
    )
    (net (code "122") (name "unconnected-(U19A-PH0-OSC_IN(PH0)-Pad12)") (class "Default")
      (node (ref "U19") (pin "12") (pinfunction "PH0-OSC_IN(PH0)_12") (pintype "bidirectional"))
    )
    (net (code "123") (name "unconnected-(U19A-PH1-OSC_OUT(PH1)-Pad13)") (class "Default")
      (node (ref "U19") (pin "13") (pinfunction "PH1-OSC_OUT(PH1)_13") (pintype "bidirectional"))
    )
    (net (code "124") (name "unconnected-(U19A-VCAP_1-Pad49)") (class "Default")
      (node (ref "U19") (pin "49") (pinfunction "VCAP_1_49") (pintype "power_in"))
    )
    (net (code "125") (name "unconnected-(U19A-VCAP_2-Pad73)") (class "Default")
      (node (ref "U19") (pin "73") (pinfunction "VCAP_2_73") (pintype "power_in"))
    )
    (net (code "126") (name "unconnected-(U19B-VBAT-Pad6)") (class "Default")
      (node (ref "U19") (pin "6") (pinfunction "VBAT_6") (pintype "power_in"))
    )
    (net (code "127") (name "unconnected-(U19B-VDD-Pad11)") (class "Default")
      (node (ref "U19") (pin "11") (pinfunction "VDD_11") (pintype "power_in"))
    )
    (net (code "128") (name "unconnected-(U19B-VDD-Pad19)") (class "Default")
      (node (ref "U19") (pin "19") (pinfunction "VDD_19") (pintype "power_in"))
    )
    (net (code "129") (name "unconnected-(U19B-VDD-Pad28)") (class "Default")
      (node (ref "U19") (pin "28") (pinfunction "VDD_28") (pintype "power_in"))
    )
    (net (code "130") (name "unconnected-(U19B-VDD-Pad50)") (class "Default")
      (node (ref "U19") (pin "50") (pinfunction "VDD_50") (pintype "power_in"))
    )
    (net (code "131") (name "unconnected-(U19B-VDD-Pad75)") (class "Default")
      (node (ref "U19") (pin "75") (pinfunction "VDD_75") (pintype "power_in"))
    )
    (net (code "132") (name "unconnected-(U19B-VDD-Pad100)") (class "Default")
      (node (ref "U19") (pin "100") (pinfunction "VDD_100") (pintype "power_in"))
    )
    (net (code "133") (name "unconnected-(U19B-VDDA-Pad22)") (class "Default")
      (node (ref "U19") (pin "22") (pinfunction "VDDA_22") (pintype "power_in"))
    )
    (net (code "134") (name "unconnected-(U19B-VREF+-Pad21)") (class "Default")
      (node (ref "U19") (pin "21") (pinfunction "VREF+_21") (pintype "power_in"))
    )
    (net (code "135") (name "unconnected-(U19B-VSS-Pad10)") (class "Default")
      (node (ref "U19") (pin "10") (pinfunction "VSS_10") (pintype "power_in"))
    )
    (net (code "136") (name "unconnected-(U19B-VSS-Pad27)") (class "Default")
      (node (ref "U19") (pin "27") (pinfunction "VSS_27") (pintype "power_in"))
    )
    (net (code "137") (name "unconnected-(U19B-VSS-Pad74)") (class "Default")
      (node (ref "U19") (pin "74") (pinfunction "VSS_74") (pintype "power_in"))
    )
    (net (code "138") (name "unconnected-(U19B-VSS-Pad99)") (class "Default")
      (node (ref "U19") (pin "99") (pinfunction "VSS_99") (pintype "power_in"))
    )
    (net (code "139") (name "unconnected-(U19B-VSSA-Pad20)") (class "Default")
      (node (ref "U19") (pin "20") (pinfunction "VSSA_20") (pintype "power_in"))
    )
  )
)
